# io.net
KiCad netlist of a schematic drawn in Altium Designer
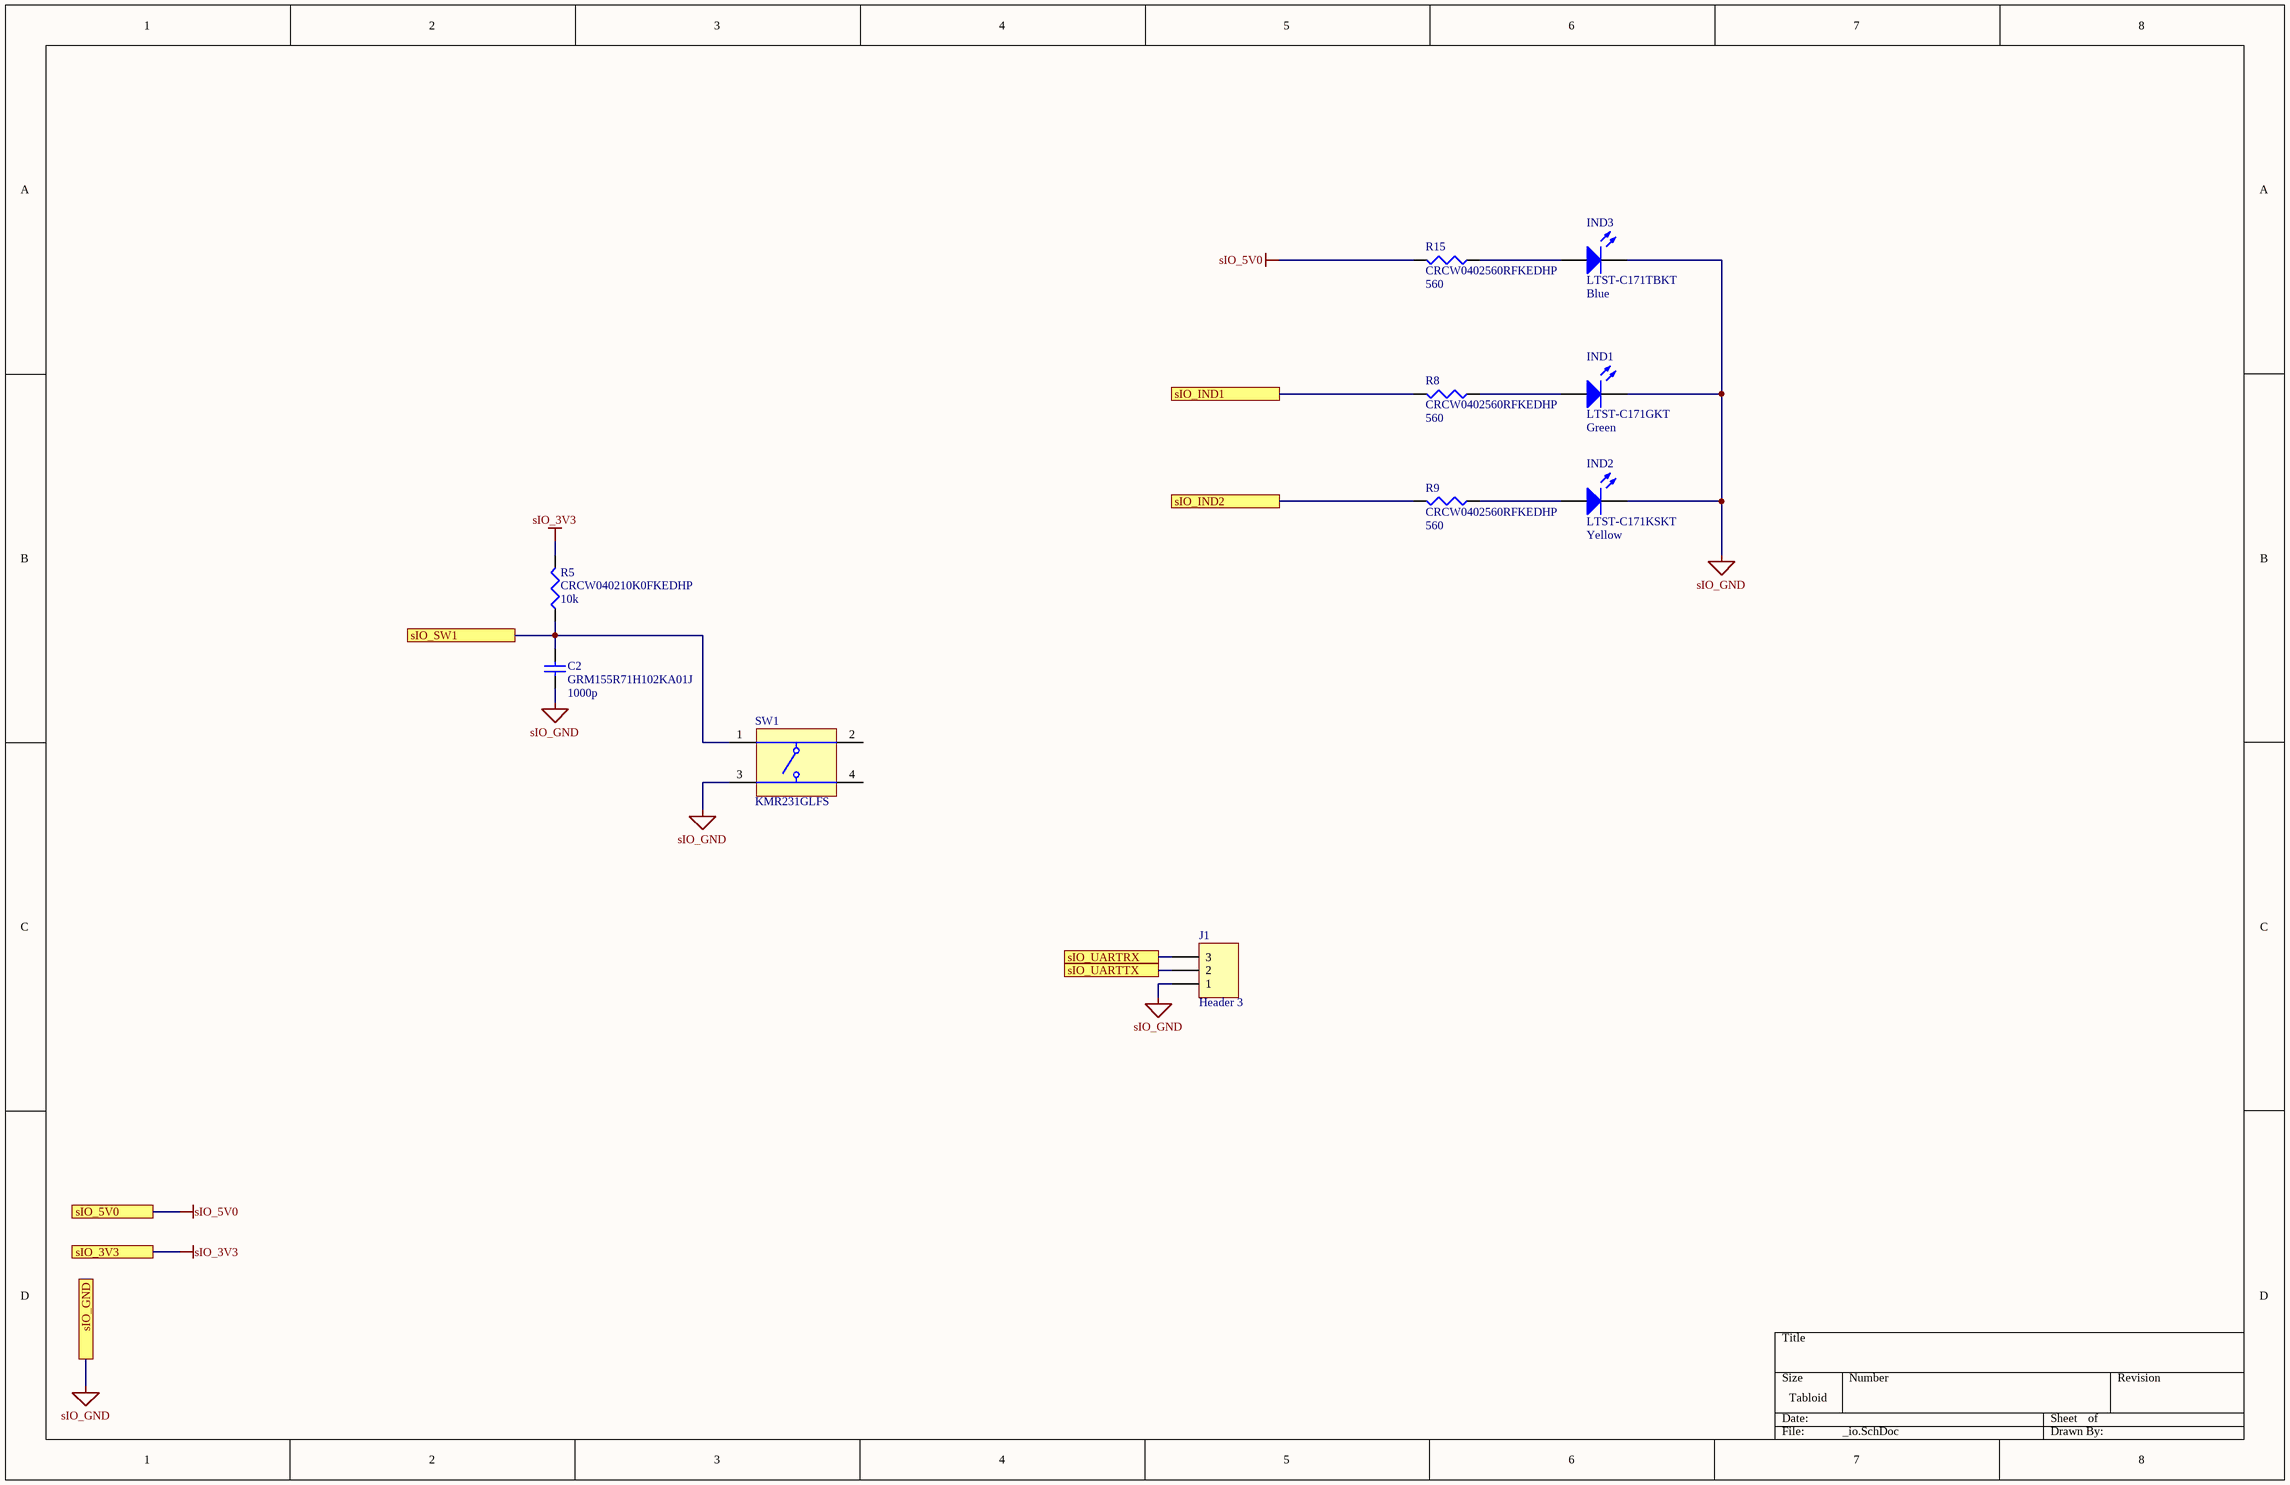
[diagram p0: _io.SchDoc]

(export (version "E")
  (design (tool "Eeschema 10.0.6"))
  (components
    (comp (ref "C2")
      (value "GRM155R71H102KA01J")
      (footprint "0402")
      (description "-55-125C, 1005, 50V, X7R, ±10%")
      (fields (field (name "ALTIUM_VALUE") "1000p"))
      (libsource (lib "standard_capacitors") (part "GRM155R71HxxxKdddd"))
    )
    (comp (ref "IND1")
      (value "LTST-C171GKT")
      (footprint "0805")
      (description "LED")
      (fields (field (name "COLOR") "Green"))
      (libsource (lib "lite-on") (part "LTST-C171GKT"))
    )
    (comp (ref "IND2")
      (value "LTST-C171KSKT")
      (footprint "0805")
      (description "LED")
      (fields (field (name "COLOR") "Yellow"))
      (libsource (lib "lite-on") (part "LTST-C171KSKT"))
    )
    (comp (ref "IND3")
      (value "LTST-C171TBKT")
      (footprint "0805")
      (description "LED")
      (fields (field (name "COLOR") "Blue"))
      (libsource (lib "lite-on") (part "LTST-C171GKT"))
    )
    (comp (ref "J1")
      (value "Header 3")
      (footprint "HDR1X3")
      (description "Header, 3-Pin")
      (fields (field (name "PUBLISHER") "Altium Limited"))
      (libsource (lib "Miscellaneous Connectors") (part "Header 3"))
    )
    (comp (ref "R5")
      (value "CRCW040210K0FKEDHP")
      (footprint "0402")
      (description "0.125W, -55-155C, 1005, 50V, ±1%")
      (fields (field (name "ALTIUM_VALUE") "10k"))
      (libsource (lib "standard_resistors") (part "CRCW0402xxxxFKED"))
    )
    (comp (ref "R8")
      (value "CRCW0402560RFKEDHP")
      (footprint "0402")
      (description "0.125W, -55-155C, 1005, 50V, ±1%")
      (fields (field (name "ALTIUM_VALUE") "560"))
      (libsource (lib "standard_resistors") (part "CRCW0402xxxxFKED"))
    )
    (comp (ref "R9")
      (value "CRCW0402560RFKEDHP")
      (footprint "0402")
      (description "0.125W, -55-155C, 1005, 50V, ±1%")
      (fields (field (name "ALTIUM_VALUE") "560"))
      (libsource (lib "standard_resistors") (part "CRCW0402xxxxFKED"))
    )
    (comp (ref "R15")
      (value "CRCW0402560RFKEDHP")
      (footprint "0402")
      (description "0.125W, -55-155C, 1005, 50V, ±1%")
      (fields (field (name "ALTIUM_VALUE") "560"))
      (libsource (lib "standard_resistors") (part "CRCW0402xxxxFKED"))
    )
    (comp (ref "SW1")
      (value "KMR231GLFS")
      (footprint "KMR231GLFS")
      (description "Switch Tactile, SPST, 50 mA, 32 V, -40 to 85 degC, 4-Pin SMD, RoHS, Tape and Reel")
      (fields (field (name "MANUFACTURER") "C&K Components"))
      (libsource (lib "candk") (part "KMR231GLFS"))
    )
  )
  (nets
    (net (code "1") (name "/sIO_IND1") (class "Default")
      (node (ref "R8") (pin "2") (pinfunction "2_2") (pintype "passive"))
    )
    (net (code "2") (name "/sIO_IND2") (class "Default")
      (node (ref "R9") (pin "2") (pinfunction "2_2") (pintype "passive"))
    )
    (net (code "3") (name "/sIO_SW1") (class "Default")
      (node (ref "C2") (pin "2") (pinfunction "2_2") (pintype "passive"))
      (node (ref "R5") (pin "1") (pinfunction "1_1") (pintype "passive"))
      (node (ref "SW1") (pin "1") (pinfunction "1_1") (pintype "passive"))
    )
    (net (code "4") (name "/sIO_UARTRX") (class "Default")
      (node (ref "J1") (pin "3") (pinfunction "3_3") (pintype "passive"))
    )
    (net (code "5") (name "/sIO_UARTTX") (class "Default")
      (node (ref "J1") (pin "2") (pinfunction "2_2") (pintype "passive"))
    )
    (net (code "6") (name "Net-(IND1-A)") (class "Default")
      (node (ref "IND1") (pin "1") (pinfunction "A_1") (pintype "passive"))
      (node (ref "R8") (pin "1") (pinfunction "1_1") (pintype "passive"))
    )
    (net (code "7") (name "Net-(IND2-A)") (class "Default")
      (node (ref "IND2") (pin "1") (pinfunction "A_1") (pintype "passive"))
      (node (ref "R9") (pin "1") (pinfunction "1_1") (pintype "passive"))
    )
    (net (code "8") (name "Net-(IND3-A)") (class "Default")
      (node (ref "IND3") (pin "1") (pinfunction "A_1") (pintype "passive"))
      (node (ref "R15") (pin "1") (pinfunction "1_1") (pintype "passive"))
    )
    (net (code "9") (name "sIO_3V3") (class "Default")
      (node (ref "R5") (pin "2") (pinfunction "2_2") (pintype "passive"))
    )
    (net (code "10") (name "sIO_5V0") (class "Default")
      (node (ref "R15") (pin "2") (pinfunction "2_2") (pintype "passive"))
    )
    (net (code "11") (name "sIO_GND") (class "Default")
      (node (ref "C2") (pin "1") (pinfunction "1_1") (pintype "passive"))
      (node (ref "IND1") (pin "2") (pinfunction "K_2") (pintype "passive"))
      (node (ref "IND2") (pin "2") (pinfunction "K_2") (pintype "passive"))
      (node (ref "IND3") (pin "2") (pinfunction "K_2") (pintype "passive"))
      (node (ref "J1") (pin "1") (pinfunction "1_1") (pintype "passive"))
      (node (ref "SW1") (pin "3") (pinfunction "3_3") (pintype "passive"))
    )
    (net (code "12") (name "unconnected-(SW1-Pad2)") (class "Default")
      (node (ref "SW1") (pin "2") (pinfunction "2_2") (pintype "passive"))
    )
    (net (code "13") (name "unconnected-(SW1-Pad4)") (class "Default")
      (node (ref "SW1") (pin "4") (pinfunction "4_4") (pintype "passive"))
    )
  )
)
